# ui.net
KiCad netlist of a schematic drawn in Altium Designer
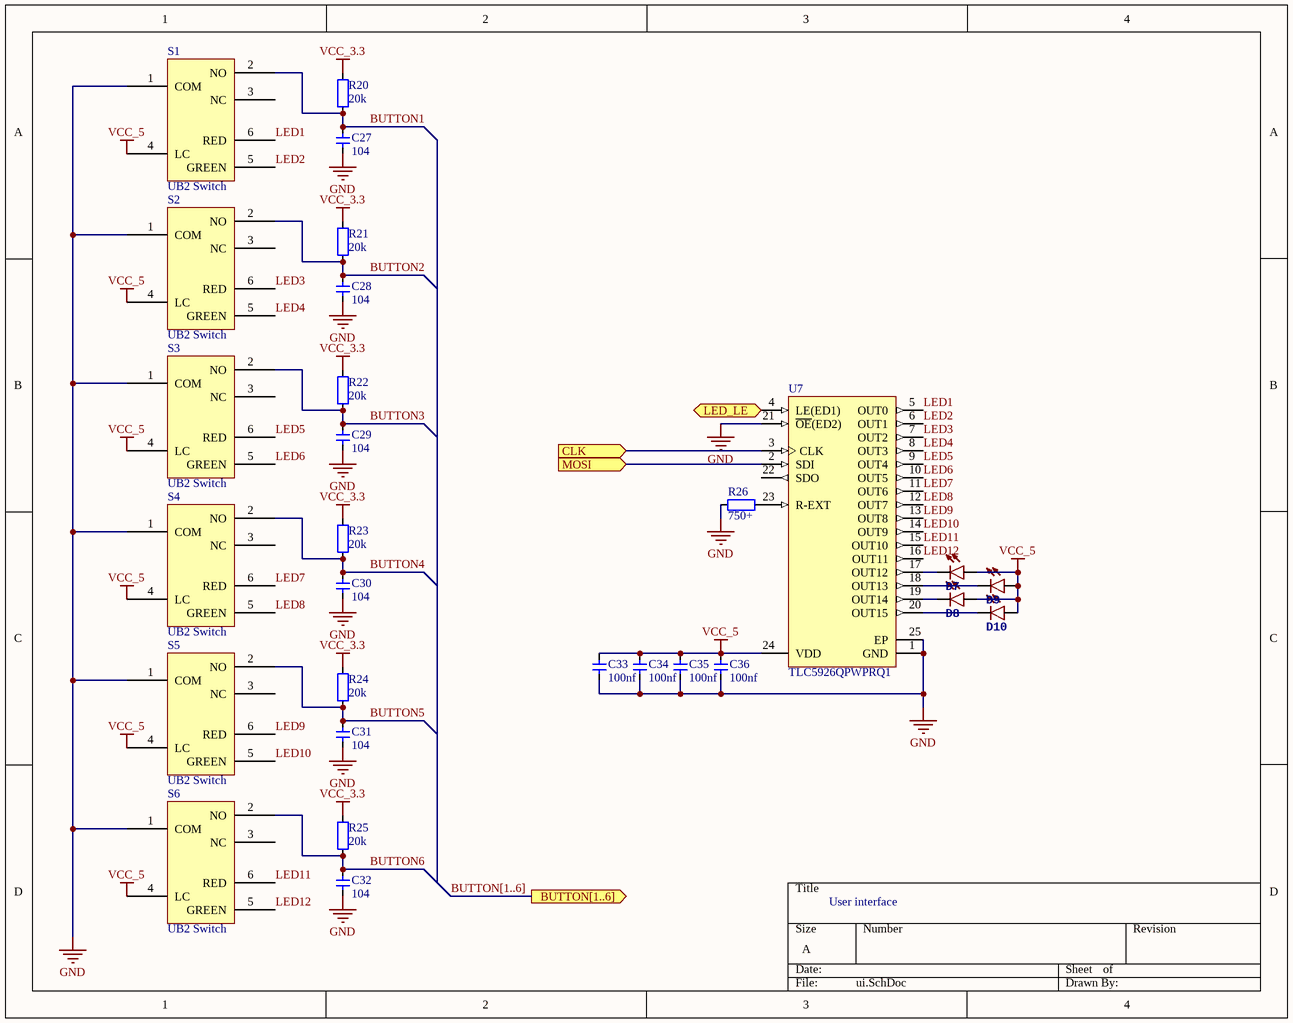
[diagram p0: ui.SchDoc]

(export (version "E")
  (design (tool "Eeschema 10.0.6"))
  (components
    (comp (ref "C27")
      (value "104")
      (footprint "PCB_PassiveCap:CAP_0603")
      (description "Capacitor")
      (fields (field (name "Comment") "Cap_0603"))
      (libsource (lib "SCH_Passive") (part "Cap_0603"))
    )
    (comp (ref "C28")
      (value "104")
      (footprint "PCB_PassiveCap:CAP_0603")
      (description "Capacitor")
      (fields (field (name "Comment") "Cap_0603"))
      (libsource (lib "SCH_Passive") (part "Cap_0603"))
    )
    (comp (ref "C29")
      (value "104")
      (footprint "PCB_PassiveCap:CAP_0603")
      (description "Capacitor")
      (fields (field (name "Comment") "Cap_0603"))
      (libsource (lib "SCH_Passive") (part "Cap_0603"))
    )
    (comp (ref "C30")
      (value "104")
      (footprint "PCB_PassiveCap:CAP_0603")
      (description "Capacitor")
      (fields (field (name "Comment") "Cap_0603"))
      (libsource (lib "SCH_Passive") (part "Cap_0603"))
    )
    (comp (ref "C31")
      (value "104")
      (footprint "PCB_PassiveCap:CAP_0603")
      (description "Capacitor")
      (fields (field (name "Comment") "Cap_0603"))
      (libsource (lib "SCH_Passive") (part "Cap_0603"))
    )
    (comp (ref "C32")
      (value "104")
      (footprint "PCB_PassiveCap:CAP_0603")
      (description "Capacitor")
      (fields (field (name "Comment") "Cap_0603"))
      (libsource (lib "SCH_Passive") (part "Cap_0603"))
    )
    (comp (ref "C33")
      (value "100nf")
      (footprint "PCB_PassiveCap:CAP_0603")
      (description "Capacitor")
      (fields (field (name "Comment") "Cap_0603"))
      (libsource (lib "SCH_Passive") (part "Cap_0603"))
    )
    (comp (ref "C34")
      (value "100nf")
      (footprint "PCB_PassiveCap:CAP_0603")
      (description "Capacitor")
      (fields (field (name "Comment") "Cap_0603"))
      (libsource (lib "SCH_Passive") (part "Cap_0603"))
    )
    (comp (ref "C35")
      (value "100nf")
      (footprint "PCB_PassiveCap:CAP_0603")
      (description "Capacitor")
      (fields (field (name "Comment") "Cap_0603"))
      (libsource (lib "SCH_Passive") (part "Cap_0603"))
    )
    (comp (ref "C36")
      (value "100nf")
      (footprint "PCB_PassiveCap:CAP_0603")
      (description "Capacitor")
      (fields (field (name "Comment") "Cap_0603"))
      (libsource (lib "SCH_Passive") (part "Cap_0603"))
    )
    (comp (ref "D7") (value "~") (footprint "LED3MM") (libsource (lib "SparkFun-LED") (part "LED3MM")))
    (comp (ref "D8") (value "~") (footprint "LED3MM") (libsource (lib "SparkFun-LED") (part "LED3MM")))
    (comp (ref "D9") (value "~") (footprint "LED3MM") (libsource (lib "SparkFun-LED") (part "LED3MM")))
    (comp (ref "D10") (value "~") (footprint "LED3MM") (libsource (lib "SparkFun-LED") (part "LED3MM")))
    (comp (ref "R20")
      (value "20k")
      (footprint "PCB_PassiveRes:RES_0603")
      (description "Resistor")
      (fields (field (name "Comment") "Res_0603"))
      (libsource (lib "SCH_Passive") (part "Res_0603"))
    )
    (comp (ref "R21")
      (value "20k")
      (footprint "PCB_PassiveRes:RES_0603")
      (description "Resistor")
      (fields (field (name "Comment") "Res_0603"))
      (libsource (lib "SCH_Passive") (part "Res_0603"))
    )
    (comp (ref "R22")
      (value "20k")
      (footprint "PCB_PassiveRes:RES_0603")
      (description "Resistor")
      (fields (field (name "Comment") "Res_0603"))
      (libsource (lib "SCH_Passive") (part "Res_0603"))
    )
    (comp (ref "R23")
      (value "20k")
      (footprint "PCB_PassiveRes:RES_0603")
      (description "Resistor")
      (fields (field (name "Comment") "Res_0603"))
      (libsource (lib "SCH_Passive") (part "Res_0603"))
    )
    (comp (ref "R24")
      (value "20k")
      (footprint "PCB_PassiveRes:RES_0603")
      (description "Resistor")
      (fields (field (name "Comment") "Res_0603"))
      (libsource (lib "SCH_Passive") (part "Res_0603"))
    )
    (comp (ref "R25")
      (value "20k")
      (footprint "PCB_PassiveRes:RES_0603")
      (description "Resistor")
      (fields (field (name "Comment") "Res_0603"))
      (libsource (lib "SCH_Passive") (part "Res_0603"))
    )
    (comp (ref "R26")
      (value "750+")
      (footprint "PCB_PassiveRes:RES_0603")
      (description "Resistor")
      (fields (field (name "Comment") "Res_0603"))
      (libsource (lib "") (part "Res_0603_1"))
    )
    (comp (ref "S1")
      (value "UB2 Switch")
      (footprint "EXTRON CLICKY")
      (libsource (lib "Schlib1") (part "EXTRON CLICKY"))
    )
    (comp (ref "S2")
      (value "UB2 Switch")
      (footprint "EXTRON CLICKY")
      (libsource (lib "Schlib1") (part "EXTRON CLICKY"))
    )
    (comp (ref "S3")
      (value "UB2 Switch")
      (footprint "EXTRON CLICKY")
      (libsource (lib "Schlib1") (part "EXTRON CLICKY"))
    )
    (comp (ref "S4")
      (value "UB2 Switch")
      (footprint "EXTRON CLICKY")
      (libsource (lib "Schlib1") (part "EXTRON CLICKY"))
    )
    (comp (ref "S5")
      (value "UB2 Switch")
      (footprint "EXTRON CLICKY")
      (libsource (lib "Schlib1") (part "EXTRON CLICKY"))
    )
    (comp (ref "S6")
      (value "UB2 Switch")
      (footprint "EXTRON CLICKY")
      (libsource (lib "Schlib1") (part "EXTRON CLICKY"))
    )
    (comp (ref "U7")
      (value "TLC5926QPWPRQ1")
      (footprint "TI-PWP24-4420X1950TP_N")
      (fields (field (name "MANUFACTURER") "Texas Instruments"))
      (libsource (lib "TI Power Management Lighting and Display") (part "TLC5926QPWPRQ1"))
    )
  )
  (nets
    (net (code "1") (name "/BUTTON1") (class "Default")
      (node (ref "C27") (pin "2") (pinfunction "2_2") (pintype "passive"))
      (node (ref "R20") (pin "1") (pinfunction "1_1") (pintype "passive"))
      (node (ref "S1") (pin "2") (pinfunction "NO_2") (pintype "passive"))
    )
    (net (code "2") (name "/BUTTON2") (class "Default")
      (node (ref "C28") (pin "2") (pinfunction "2_2") (pintype "passive"))
      (node (ref "R21") (pin "1") (pinfunction "1_1") (pintype "passive"))
      (node (ref "S2") (pin "2") (pinfunction "NO_2") (pintype "passive"))
    )
    (net (code "3") (name "/BUTTON3") (class "Default")
      (node (ref "C29") (pin "2") (pinfunction "2_2") (pintype "passive"))
      (node (ref "R22") (pin "1") (pinfunction "1_1") (pintype "passive"))
      (node (ref "S3") (pin "2") (pinfunction "NO_2") (pintype "passive"))
    )
    (net (code "4") (name "/BUTTON4") (class "Default")
      (node (ref "C30") (pin "2") (pinfunction "2_2") (pintype "passive"))
      (node (ref "R23") (pin "1") (pinfunction "1_1") (pintype "passive"))
      (node (ref "S4") (pin "2") (pinfunction "NO_2") (pintype "passive"))
    )
    (net (code "5") (name "/BUTTON5") (class "Default")
      (node (ref "C31") (pin "2") (pinfunction "2_2") (pintype "passive"))
      (node (ref "R24") (pin "1") (pinfunction "1_1") (pintype "passive"))
      (node (ref "S5") (pin "2") (pinfunction "NO_2") (pintype "passive"))
    )
    (net (code "6") (name "/BUTTON6") (class "Default")
      (node (ref "C32") (pin "2") (pinfunction "2_2") (pintype "passive"))
      (node (ref "R25") (pin "1") (pinfunction "1_1") (pintype "passive"))
      (node (ref "S6") (pin "2") (pinfunction "NO_2") (pintype "passive"))
    )
    (net (code "8") (name "/CLK") (class "Default")
      (node (ref "U7") (pin "3") (pinfunction "CLK_3") (pintype "input"))
    )
    (net (code "9") (name "/LED1") (class "Default")
      (node (ref "S1") (pin "6") (pinfunction "RED_6") (pintype "passive"))
      (node (ref "U7") (pin "5") (pinfunction "OUT0_5") (pintype "output"))
    )
    (net (code "10") (name "/LED2") (class "Default")
      (node (ref "S1") (pin "5") (pinfunction "GREEN_5") (pintype "passive"))
      (node (ref "U7") (pin "6") (pinfunction "OUT1_6") (pintype "output"))
    )
    (net (code "11") (name "/LED3") (class "Default")
      (node (ref "S2") (pin "6") (pinfunction "RED_6") (pintype "passive"))
      (node (ref "U7") (pin "7") (pinfunction "OUT2_7") (pintype "output"))
    )
    (net (code "12") (name "/LED4") (class "Default")
      (node (ref "S2") (pin "5") (pinfunction "GREEN_5") (pintype "passive"))
      (node (ref "U7") (pin "8") (pinfunction "OUT3_8") (pintype "output"))
    )
    (net (code "13") (name "/LED5") (class "Default")
      (node (ref "S3") (pin "6") (pinfunction "RED_6") (pintype "passive"))
      (node (ref "U7") (pin "9") (pinfunction "OUT4_9") (pintype "output"))
    )
    (net (code "14") (name "/LED6") (class "Default")
      (node (ref "S3") (pin "5") (pinfunction "GREEN_5") (pintype "passive"))
      (node (ref "U7") (pin "10") (pinfunction "OUT5_10") (pintype "output"))
    )
    (net (code "15") (name "/LED7") (class "Default")
      (node (ref "S4") (pin "6") (pinfunction "RED_6") (pintype "passive"))
      (node (ref "U7") (pin "11") (pinfunction "OUT6_11") (pintype "output"))
    )
    (net (code "16") (name "/LED8") (class "Default")
      (node (ref "S4") (pin "5") (pinfunction "GREEN_5") (pintype "passive"))
      (node (ref "U7") (pin "12") (pinfunction "OUT7_12") (pintype "output"))
    )
    (net (code "17") (name "/LED9") (class "Default")
      (node (ref "S5") (pin "6") (pinfunction "RED_6") (pintype "passive"))
      (node (ref "U7") (pin "13") (pinfunction "OUT8_13") (pintype "output"))
    )
    (net (code "18") (name "/LED10") (class "Default")
      (node (ref "S5") (pin "5") (pinfunction "GREEN_5") (pintype "passive"))
      (node (ref "U7") (pin "14") (pinfunction "OUT9_14") (pintype "output"))
    )
    (net (code "19") (name "/LED11") (class "Default")
      (node (ref "S6") (pin "6") (pinfunction "RED_6") (pintype "passive"))
      (node (ref "U7") (pin "15") (pinfunction "OUT10_15") (pintype "output"))
    )
    (net (code "20") (name "/LED12") (class "Default")
      (node (ref "S6") (pin "5") (pinfunction "GREEN_5") (pintype "passive"))
      (node (ref "U7") (pin "16") (pinfunction "OUT11_16") (pintype "output"))
    )
    (net (code "21") (name "/LED_LE") (class "Default")
      (node (ref "U7") (pin "4") (pinfunction "LE(ED1)_4") (pintype "input"))
    )
    (net (code "22") (name "/MOSI") (class "Default")
      (node (ref "U7") (pin "2") (pinfunction "SDI_2") (pintype "input"))
    )
    (net (code "23") (name "GND") (class "Default")
      (node (ref "C27") (pin "1") (pinfunction "1_1") (pintype "passive"))
      (node (ref "C28") (pin "1") (pinfunction "1_1") (pintype "passive"))
      (node (ref "C29") (pin "1") (pinfunction "1_1") (pintype "passive"))
      (node (ref "C30") (pin "1") (pinfunction "1_1") (pintype "passive"))
      (node (ref "C31") (pin "1") (pinfunction "1_1") (pintype "passive"))
      (node (ref "C32") (pin "1") (pinfunction "1_1") (pintype "passive"))
      (node (ref "C33") (pin "1") (pinfunction "1_1") (pintype "passive"))
      (node (ref "C34") (pin "1") (pinfunction "1_1") (pintype "passive"))
      (node (ref "C35") (pin "1") (pinfunction "1_1") (pintype "passive"))
      (node (ref "C36") (pin "1") (pinfunction "1_1") (pintype "passive"))
      (node (ref "R26") (pin "2") (pinfunction "2_2") (pintype "passive"))
      (node (ref "S1") (pin "1") (pinfunction "COM_1") (pintype "passive"))
      (node (ref "S2") (pin "1") (pinfunction "COM_1") (pintype "passive"))
      (node (ref "S3") (pin "1") (pinfunction "COM_1") (pintype "passive"))
      (node (ref "S4") (pin "1") (pinfunction "COM_1") (pintype "passive"))
      (node (ref "S5") (pin "1") (pinfunction "COM_1") (pintype "passive"))
      (node (ref "S6") (pin "1") (pinfunction "COM_1") (pintype "passive"))
      (node (ref "U7") (pin "1") (pinfunction "GND_1") (pintype "power_in"))
      (node (ref "U7") (pin "21") (pinfunction "~{OE}(ED2)_21") (pintype "input"))
      (node (ref "U7") (pin "25") (pinfunction "EP_25") (pintype "power_in"))
    )
    (net (code "24") (name "Net-(D7-C)") (class "Default")
      (node (ref "D7") (pin "K") (pinfunction "C_K") (pintype "passive"))
      (node (ref "U7") (pin "17") (pinfunction "OUT12_17") (pintype "output"))
    )
    (net (code "25") (name "Net-(D8-C)") (class "Default")
      (node (ref "D8") (pin "K") (pinfunction "C_K") (pintype "passive"))
      (node (ref "U7") (pin "19") (pinfunction "OUT14_19") (pintype "output"))
    )
    (net (code "26") (name "Net-(D9-C)") (class "Default")
      (node (ref "D9") (pin "K") (pinfunction "C_K") (pintype "passive"))
      (node (ref "U7") (pin "18") (pinfunction "OUT13_18") (pintype "output"))
    )
    (net (code "27") (name "Net-(D10-C)") (class "Default")
      (node (ref "D10") (pin "K") (pinfunction "C_K") (pintype "passive"))
      (node (ref "U7") (pin "20") (pinfunction "OUT15_20") (pintype "output"))
    )
    (net (code "28") (name "Net-(U7-R-EXT)") (class "Default")
      (node (ref "R26") (pin "1") (pinfunction "1_1") (pintype "passive"))
      (node (ref "U7") (pin "23") (pinfunction "R-EXT_23") (pintype "input"))
    )
    (net (code "29") (name "VCC_3.3") (class "Default")
      (node (ref "R20") (pin "2") (pinfunction "2_2") (pintype "passive"))
      (node (ref "R21") (pin "2") (pinfunction "2_2") (pintype "passive"))
      (node (ref "R22") (pin "2") (pinfunction "2_2") (pintype "passive"))
      (node (ref "R23") (pin "2") (pinfunction "2_2") (pintype "passive"))
      (node (ref "R24") (pin "2") (pinfunction "2_2") (pintype "passive"))
      (node (ref "R25") (pin "2") (pinfunction "2_2") (pintype "passive"))
    )
    (net (code "30") (name "VCC_5") (class "Default")
      (node (ref "C33") (pin "2") (pinfunction "2_2") (pintype "passive"))
      (node (ref "C34") (pin "2") (pinfunction "2_2") (pintype "passive"))
      (node (ref "C35") (pin "2") (pinfunction "2_2") (pintype "passive"))
      (node (ref "C36") (pin "2") (pinfunction "2_2") (pintype "passive"))
      (node (ref "D10") (pin "A") (pinfunction "A_A") (pintype "passive"))
      (node (ref "D7") (pin "A") (pinfunction "A_A") (pintype "passive"))
      (node (ref "D8") (pin "A") (pinfunction "A_A") (pintype "passive"))
      (node (ref "D9") (pin "A") (pinfunction "A_A") (pintype "passive"))
      (node (ref "S1") (pin "4") (pinfunction "LC_4") (pintype "passive"))
      (node (ref "S2") (pin "4") (pinfunction "LC_4") (pintype "passive"))
      (node (ref "S3") (pin "4") (pinfunction "LC_4") (pintype "passive"))
      (node (ref "S4") (pin "4") (pinfunction "LC_4") (pintype "passive"))
      (node (ref "S5") (pin "4") (pinfunction "LC_4") (pintype "passive"))
      (node (ref "S6") (pin "4") (pinfunction "LC_4") (pintype "passive"))
      (node (ref "U7") (pin "24") (pinfunction "VDD_24") (pintype "power_in"))
    )
    (net (code "31") (name "unconnected-(S1-NC-Pad3)") (class "Default")
      (node (ref "S1") (pin "3") (pinfunction "NC_3") (pintype "passive"))
    )
    (net (code "32") (name "unconnected-(S2-NC-Pad3)") (class "Default")
      (node (ref "S2") (pin "3") (pinfunction "NC_3") (pintype "passive"))
    )
    (net (code "33") (name "unconnected-(S3-NC-Pad3)") (class "Default")
      (node (ref "S3") (pin "3") (pinfunction "NC_3") (pintype "passive"))
    )
    (net (code "34") (name "unconnected-(S4-NC-Pad3)") (class "Default")
      (node (ref "S4") (pin "3") (pinfunction "NC_3") (pintype "passive"))
    )
    (net (code "35") (name "unconnected-(S5-NC-Pad3)") (class "Default")
      (node (ref "S5") (pin "3") (pinfunction "NC_3") (pintype "passive"))
    )
    (net (code "36") (name "unconnected-(S6-NC-Pad3)") (class "Default")
      (node (ref "S6") (pin "3") (pinfunction "NC_3") (pintype "passive"))
    )
    (net (code "37") (name "unconnected-(U7-SDO-Pad22)") (class "Default")
      (node (ref "U7") (pin "22") (pinfunction "SDO_22") (pintype "output"))
    )
  )
)
